# MiniCar.net
KiCad netlist of a schematic drawn in Altium Designer
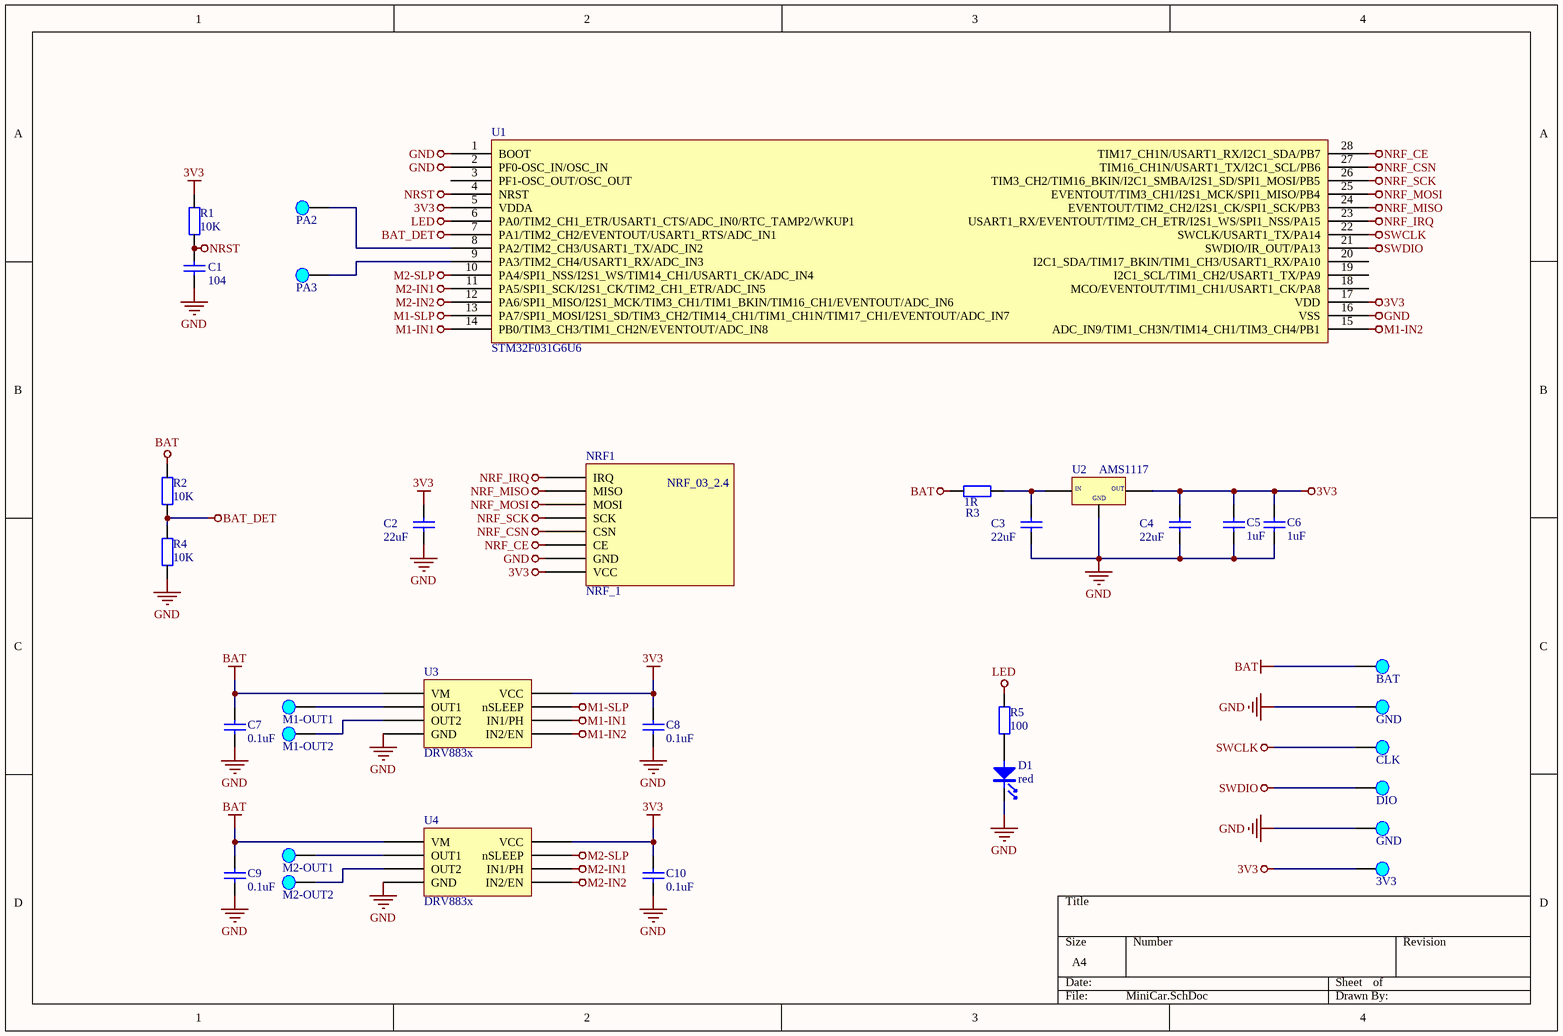
[diagram p0: MiniCar.SchDoc]

(export (version "E")
  (design (tool "Eeschema 10.0.6"))
  (components
    (comp (ref "3V3")
      (value "3V3")
      (footprint "Pad_B")
      (fields (field (name "_REMARKS") "3V3"))
      (libsource (lib "元件库") (part "Pad"))
    )
    (comp (ref "BAT")
      (value "BAT")
      (footprint "Pad_B")
      (fields (field (name "_REMARKS") "BAT"))
      (libsource (lib "元件库") (part "Pad"))
    )
    (comp (ref "C1")
      (value "104")
      (footprint "电容_C0603")
      (fields (field (name "C") "104"))
      (libsource (lib "元件库") (part "cap"))
    )
    (comp (ref "C2")
      (value "22uF")
      (footprint "电容_C1206")
      (fields (field (name "C") "22uF"))
      (libsource (lib "元件库") (part "cap"))
    )
    (comp (ref "C3")
      (value "22uF")
      (footprint "电容_C1206")
      (fields (field (name "C") "22uF"))
      (libsource (lib "元件库") (part "cap"))
    )
    (comp (ref "C4")
      (value "22uF")
      (footprint "电容_C1206")
      (fields (field (name "C") "22uF"))
      (libsource (lib "元件库") (part "cap"))
    )
    (comp (ref "C5")
      (value "1uF")
      (footprint "电容_C0603")
      (fields (field (name "C") "1uF"))
      (libsource (lib "元件库") (part "cap"))
    )
    (comp (ref "C6")
      (value "1uF")
      (footprint "电容_C0603")
      (fields (field (name "C") "1uF"))
      (libsource (lib "元件库") (part "cap"))
    )
    (comp (ref "C7")
      (value "0.1uF")
      (footprint "电容_C0603")
      (fields (field (name "C") "0.1uF"))
      (libsource (lib "元件库") (part "cap"))
    )
    (comp (ref "C8")
      (value "0.1uF")
      (footprint "电容_C0603")
      (fields (field (name "C") "0.1uF"))
      (libsource (lib "元件库") (part "cap"))
    )
    (comp (ref "C9")
      (value "0.1uF")
      (footprint "电容_C0603")
      (fields (field (name "C") "0.1uF"))
      (libsource (lib "元件库") (part "cap"))
    )
    (comp (ref "C10")
      (value "0.1uF")
      (footprint "电容_C0603")
      (fields (field (name "C") "0.1uF"))
      (libsource (lib "元件库") (part "cap"))
    )
    (comp (ref "CLK")
      (value "CLK")
      (footprint "Pad_B")
      (fields (field (name "_REMARKS") "CLK"))
      (libsource (lib "元件库") (part "Pad"))
    )
    (comp (ref "D1") (value "red") (footprint "LED_0603") (libsource (lib "元件库") (part "LED")))
    (comp (ref "DIO")
      (value "DIO")
      (footprint "Pad_B")
      (fields (field (name "_REMARKS") "DIO"))
      (libsource (lib "元件库") (part "Pad"))
    )
    (comp (ref "GND")
      (value "GND")
      (footprint "Pad_B")
      (fields (field (name "_REMARKS") "GND"))
      (libsource (lib "元件库") (part "Pad"))
    )
    (comp (ref "GND2")
      (value "GND")
      (footprint "Pad_B")
      (fields (field (name "_REMARKS") "GND"))
      (libsource (lib "元件库") (part "Pad"))
    )
    (comp (ref "M1+")
      (value "M1-OUT1")
      (footprint "Pad_B")
      (fields (field (name "_REMARKS") "M1-OUT1"))
      (libsource (lib "元件库") (part "Pad"))
    )
    (comp (ref "M1-")
      (value "M1-OUT2")
      (footprint "Pad_B")
      (fields (field (name "_REMARKS") "M1-OUT2"))
      (libsource (lib "元件库") (part "Pad"))
    )
    (comp (ref "M2+")
      (value "M2-OUT1")
      (footprint "Pad_B")
      (fields (field (name "_REMARKS") "M2-OUT1"))
      (libsource (lib "元件库") (part "Pad"))
    )
    (comp (ref "M2-")
      (value "M2-OUT2")
      (footprint "Pad_B")
      (fields (field (name "_REMARKS") "M2-OUT2"))
      (libsource (lib "元件库") (part "Pad"))
    )
    (comp (ref "NRF1") (value "NRF_1") (footprint "NRF-1") (libsource (lib "Schlib1") (part "NRF_1")))
    (comp (ref "PA2")
      (value "PA2")
      (footprint "Pad_B")
      (fields (field (name "_REMARKS") "PA2"))
      (libsource (lib "元件库") (part "Pad"))
    )
    (comp (ref "PA3")
      (value "PA3")
      (footprint "Pad_B")
      (fields (field (name "_REMARKS") "PA3"))
      (libsource (lib "元件库") (part "Pad"))
    )
    (comp (ref "R1")
      (value "10K")
      (footprint "电阻_R0603")
      (fields (field (name "R") "10K"))
      (libsource (lib "") (part "Res_2"))
    )
    (comp (ref "R2")
      (value "10K")
      (footprint "电阻_R0603")
      (fields (field (name "R") "10K"))
      (libsource (lib "") (part "Res_2"))
    )
    (comp (ref "R3")
      (value "1R")
      (footprint "电阻_R0603")
      (fields (field (name "R") "1R"))
      (libsource (lib "元件库") (part "Res"))
    )
    (comp (ref "R4")
      (value "10K")
      (footprint "电阻_R0603")
      (fields (field (name "R") "10K"))
      (libsource (lib "") (part "Res_2"))
    )
    (comp (ref "R5")
      (value "100")
      (footprint "电阻_R0603")
      (fields (field (name "R") "100"))
      (libsource (lib "") (part "Res_1"))
    )
    (comp (ref "U1")
      (value "STM32F031G6U6")
      (footprint "ST主控_UFQFPN28")
      (libsource (lib "元件库") (part "STM32F031G6U6"))
    )
    (comp (ref "U2") (value "AMS1117") (footprint "稳压芯片_SOT-89") (libsource (lib "元件库") (part "AMS1117")))
    (comp (ref "U3") (value "DRV883x") (footprint "WSON-8") (libsource (lib "xSchlib") (part "DRV883x")))
    (comp (ref "U4") (value "DRV883x") (footprint "WSON-8") (libsource (lib "xSchlib") (part "DRV883x")))
  )
  (nets
    (net (code "1") (name "3V3") (class "Default")
      (node (ref "3V3") (pin "1") (pinfunction "*_1") (pintype "passive"))
      (node (ref "C10") (pin "2") (pinfunction "2_2") (pintype "passive"))
      (node (ref "C2") (pin "2") (pinfunction "2_2") (pintype "passive"))
      (node (ref "C4") (pin "2") (pinfunction "2_2") (pintype "passive"))
      (node (ref "C5") (pin "2") (pinfunction "2_2") (pintype "passive"))
      (node (ref "C6") (pin "2") (pinfunction "2_2") (pintype "passive"))
      (node (ref "C8") (pin "2") (pinfunction "2_2") (pintype "passive"))
      (node (ref "NRF1") (pin "1") (pinfunction "VCC_1") (pintype "passive"))
      (node (ref "R1") (pin "2") (pinfunction "2_2") (pintype "passive"))
      (node (ref "U1") (pin "17") (pinfunction "VDD_17") (pintype "passive"))
      (node (ref "U1") (pin "5") (pinfunction "VDDA_5") (pintype "passive"))
      (node (ref "U2") (pin "2") (pinfunction "OUT_2") (pintype "passive"))
      (node (ref "U3") (pin "8") (pinfunction "VCC_8") (pintype "passive"))
      (node (ref "U4") (pin "8") (pinfunction "VCC_8") (pintype "passive"))
    )
    (net (code "2") (name "BAT") (class "Default")
      (node (ref "BAT") (pin "1") (pinfunction "*_1") (pintype "passive"))
      (node (ref "C7") (pin "1") (pinfunction "1_1") (pintype "passive"))
      (node (ref "C9") (pin "1") (pinfunction "1_1") (pintype "passive"))
      (node (ref "R2") (pin "2") (pinfunction "2_2") (pintype "passive"))
      (node (ref "R3") (pin "1") (pinfunction "1_1") (pintype "passive"))
      (node (ref "U3") (pin "1") (pinfunction "VM_1") (pintype "passive"))
      (node (ref "U4") (pin "1") (pinfunction "VM_1") (pintype "passive"))
    )
    (net (code "3") (name "BAT_DET") (class "Default")
      (node (ref "R2") (pin "1") (pinfunction "1_1") (pintype "passive"))
      (node (ref "R4") (pin "2") (pinfunction "2_2") (pintype "passive"))
      (node (ref "U1") (pin "7") (pinfunction "PA1/TIM2_CH2/EVENTOUT/USART1_RTS/ADC_IN1_7") (pintype "passive"))
    )
    (net (code "4") (name "GND") (class "Default")
      (node (ref "C1") (pin "1") (pinfunction "1_1") (pintype "passive"))
      (node (ref "C10") (pin "1") (pinfunction "1_1") (pintype "passive"))
      (node (ref "C2") (pin "1") (pinfunction "1_1") (pintype "passive"))
      (node (ref "C3") (pin "1") (pinfunction "1_1") (pintype "passive"))
      (node (ref "C4") (pin "1") (pinfunction "1_1") (pintype "passive"))
      (node (ref "C5") (pin "1") (pinfunction "1_1") (pintype "passive"))
      (node (ref "C6") (pin "1") (pinfunction "1_1") (pintype "passive"))
      (node (ref "C7") (pin "2") (pinfunction "2_2") (pintype "passive"))
      (node (ref "C8") (pin "1") (pinfunction "1_1") (pintype "passive"))
      (node (ref "C9") (pin "2") (pinfunction "2_2") (pintype "passive"))
      (node (ref "D1") (pin "K") (pinfunction "K_K") (pintype "passive"))
      (node (ref "GND") (pin "1") (pinfunction "*_1") (pintype "passive"))
      (node (ref "GND2") (pin "1") (pinfunction "*_1") (pintype "passive"))
      (node (ref "NRF1") (pin "2") (pinfunction "GND_2") (pintype "passive"))
      (node (ref "R4") (pin "1") (pinfunction "1_1") (pintype "passive"))
      (node (ref "U1") (pin "1") (pinfunction "BOOT_1") (pintype "passive"))
      (node (ref "U1") (pin "16") (pinfunction "VSS_16") (pintype "passive"))
      (node (ref "U1") (pin "2") (pinfunction "PF0-OSC_IN/OSC_IN_2") (pintype "passive"))
      (node (ref "U2") (pin "1") (pinfunction "GND_1") (pintype "passive"))
      (node (ref "U3") (pin "4") (pinfunction "GND_4") (pintype "passive"))
      (node (ref "U4") (pin "4") (pinfunction "GND_4") (pintype "passive"))
    )
    (net (code "5") (name "LED") (class "Default")
      (node (ref "R5") (pin "1") (pinfunction "1_1") (pintype "passive"))
      (node (ref "U1") (pin "6") (pinfunction "PA0/TIM2_CH1_ETR/USART1_CTS/ADC_IN0/RTC_TAMP2/WKUP1_6") (pintype "passive"))
    )
    (net (code "6") (name "M1-IN1") (class "Default")
      (node (ref "U1") (pin "14") (pinfunction "PB0/TIM3_CH3/TIM1_CH2N/EVENTOUT/ADC_IN8_14") (pintype "passive"))
      (node (ref "U3") (pin "6") (pinfunction "IN1/PH_6") (pintype "passive"))
    )
    (net (code "7") (name "M1-IN2") (class "Default")
      (node (ref "U1") (pin "15") (pinfunction "ADC_IN9/TIM1_CH3N/TIM14_CH1/TIM3_CH4/PB1_15") (pintype "passive"))
      (node (ref "U3") (pin "5") (pinfunction "IN2/EN_5") (pintype "passive"))
    )
    (net (code "8") (name "M1-SLP") (class "Default")
      (node (ref "U1") (pin "13") (pinfunction "PA7/SPI1_MOSI/I2S1_SD/TIM3_CH2/TIM14_CH1/TIM1_CH1N/TIM17_CH1/EVENTOUT/ADC_IN7_13") (pintype "passive"))
      (node (ref "U3") (pin "7") (pinfunction "nSLEEP_7") (pintype "passive"))
    )
    (net (code "9") (name "M2-IN1") (class "Default")
      (node (ref "U1") (pin "11") (pinfunction "PA5/SPI1_SCK/I2S1_CK/TIM2_CH1_ETR/ADC_IN5_11") (pintype "passive"))
      (node (ref "U4") (pin "6") (pinfunction "IN1/PH_6") (pintype "passive"))
    )
    (net (code "10") (name "M2-IN2") (class "Default")
      (node (ref "U1") (pin "12") (pinfunction "PA6/SPI1_MISO/I2S1_MCK/TIM3_CH1/TIM1_BKIN/TIM16_CH1/EVENTOUT/ADC_IN6_12") (pintype "passive"))
      (node (ref "U4") (pin "5") (pinfunction "IN2/EN_5") (pintype "passive"))
    )
    (net (code "11") (name "M2-SLP") (class "Default")
      (node (ref "U1") (pin "10") (pinfunction "PA4/SPI1_NSS/I2S1_WS/TIM14_CH1/USART1_CK/ADC_IN4_10") (pintype "passive"))
      (node (ref "U4") (pin "7") (pinfunction "nSLEEP_7") (pintype "passive"))
    )
    (net (code "12") (name "NRF_CE") (class "Default")
      (node (ref "NRF1") (pin "3") (pinfunction "CE_3") (pintype "passive"))
      (node (ref "U1") (pin "28") (pinfunction "TIM17_CH1N/USART1_RX/I2C1_SDA/PB7_28") (pintype "passive"))
    )
    (net (code "13") (name "NRF_CSN") (class "Default")
      (node (ref "NRF1") (pin "4") (pinfunction "CSN_4") (pintype "passive"))
      (node (ref "U1") (pin "27") (pinfunction "TIM16_CH1N/USART1_TX/I2C1_SCL/PB6_27") (pintype "passive"))
    )
    (net (code "14") (name "NRF_IRQ") (class "Default")
      (node (ref "NRF1") (pin "8") (pinfunction "IRQ_8") (pintype "passive"))
      (node (ref "U1") (pin "23") (pinfunction "USART1_RX/EVENTOUT/TIM2_CH_ETR/I2S1_WS/SPI1_NSS/PA15_23") (pintype "passive"))
    )
    (net (code "15") (name "NRF_MISO") (class "Default")
      (node (ref "NRF1") (pin "7") (pinfunction "MISO_7") (pintype "passive"))
      (node (ref "U1") (pin "24") (pinfunction "EVENTOUT/TIM2_CH2/I2S1_CK/SPI1_SCK/PB3_24") (pintype "passive"))
    )
    (net (code "16") (name "NRF_MOSI") (class "Default")
      (node (ref "NRF1") (pin "6") (pinfunction "MOSI_6") (pintype "passive"))
      (node (ref "U1") (pin "25") (pinfunction "EVENTOUT/TIM3_CH1/I2S1_MCK/SPI1_MISO/PB4_25") (pintype "passive"))
    )
    (net (code "17") (name "NRF_SCK") (class "Default")
      (node (ref "NRF1") (pin "5") (pinfunction "SCK_5") (pintype "passive"))
      (node (ref "U1") (pin "26") (pinfunction "TIM3_CH2/TIM16_BKIN/I2C1_SMBA/I2S1_SD/SPI1_MOSI/PB5_26") (pintype "passive"))
    )
    (net (code "18") (name "NRST") (class "Default")
      (node (ref "C1") (pin "2") (pinfunction "2_2") (pintype "passive"))
      (node (ref "R1") (pin "1") (pinfunction "1_1") (pintype "passive"))
      (node (ref "U1") (pin "4") (pinfunction "NRST_4") (pintype "passive"))
    )
    (net (code "19") (name "Net-(D1-PadA)") (class "Default")
      (node (ref "D1") (pin "A") (pinfunction "A_A") (pintype "passive"))
      (node (ref "R5") (pin "2") (pinfunction "2_2") (pintype "passive"))
    )
    (net (code "20") (name "Net-(M1+-*)") (class "Default")
      (node (ref "M1+") (pin "1") (pinfunction "*_1") (pintype "passive"))
      (node (ref "U3") (pin "2") (pinfunction "OUT1_2") (pintype "passive"))
    )
    (net (code "21") (name "Net-(M1--*)") (class "Default")
      (node (ref "M1-") (pin "1") (pinfunction "*_1") (pintype "passive"))
      (node (ref "U3") (pin "3") (pinfunction "OUT2_3") (pintype "passive"))
    )
    (net (code "22") (name "Net-(M2+-*)") (class "Default")
      (node (ref "M2+") (pin "1") (pinfunction "*_1") (pintype "passive"))
      (node (ref "U4") (pin "2") (pinfunction "OUT1_2") (pintype "passive"))
    )
    (net (code "23") (name "Net-(M2--*)") (class "Default")
      (node (ref "M2-") (pin "1") (pinfunction "*_1") (pintype "passive"))
      (node (ref "U4") (pin "3") (pinfunction "OUT2_3") (pintype "passive"))
    )
    (net (code "24") (name "Net-(PA2-*)") (class "Default")
      (node (ref "PA2") (pin "1") (pinfunction "*_1") (pintype "passive"))
      (node (ref "U1") (pin "8") (pinfunction "PA2/TIM2_CH3/USART1_TX/ADC_IN2_8") (pintype "passive"))
    )
    (net (code "25") (name "Net-(PA3-*)") (class "Default")
      (node (ref "PA3") (pin "1") (pinfunction "*_1") (pintype "passive"))
      (node (ref "U1") (pin "9") (pinfunction "PA3/TIM2_CH4/USART1_RX/ADC_IN3_9") (pintype "passive"))
    )
    (net (code "26") (name "Net-(U2-VIN)") (class "Default")
      (node (ref "C3") (pin "2") (pinfunction "2_2") (pintype "passive"))
      (node (ref "R3") (pin "2") (pinfunction "2_2") (pintype "passive"))
      (node (ref "U2") (pin "3") (pinfunction "VIN_3") (pintype "passive"))
    )
    (net (code "27") (name "SWCLK") (class "Default")
      (node (ref "CLK") (pin "1") (pinfunction "*_1") (pintype "passive"))
      (node (ref "U1") (pin "22") (pinfunction "SWCLK/USART1_TX/PA14_22") (pintype "passive"))
    )
    (net (code "28") (name "SWDIO") (class "Default")
      (node (ref "DIO") (pin "1") (pinfunction "*_1") (pintype "passive"))
      (node (ref "U1") (pin "21") (pinfunction "SWDIO/IR_OUT/PA13_21") (pintype "passive"))
    )
    (net (code "29") (name "unconnected-(U1-I2C1_SCL{slash}TIM1_CH2{slash}USART1_TX{slash}PA9-Pad19)") (class "Default")
      (node (ref "U1") (pin "19") (pinfunction "I2C1_SCL/TIM1_CH2/USART1_TX/PA9_19") (pintype "passive"))
    )
    (net (code "30") (name "unconnected-(U1-I2C1_SDA{slash}TIM17_BKIN{slash}TIM1_CH3{slash}USART1_RX{slash}PA10-Pad20)") (class "Default")
      (node (ref "U1") (pin "20") (pinfunction "I2C1_SDA/TIM17_BKIN/TIM1_CH3/USART1_RX/PA10_20") (pintype "passive"))
    )
    (net (code "31") (name "unconnected-(U1-MCO{slash}EVENTOUT{slash}TIM1_CH1{slash}USART1_CK{slash}PA8-Pad18)") (class "Default")
      (node (ref "U1") (pin "18") (pinfunction "MCO/EVENTOUT/TIM1_CH1/USART1_CK/PA8_18") (pintype "passive"))
    )
    (net (code "32") (name "unconnected-(U1-PF1-OSC_OUT{slash}OSC_OUT-Pad3)") (class "Default")
      (node (ref "U1") (pin "3") (pinfunction "PF1-OSC_OUT/OSC_OUT_3") (pintype "passive"))
    )
  )
)
